# LedMatrix.net
KiCad netlist of a schematic drawn in EAGLE
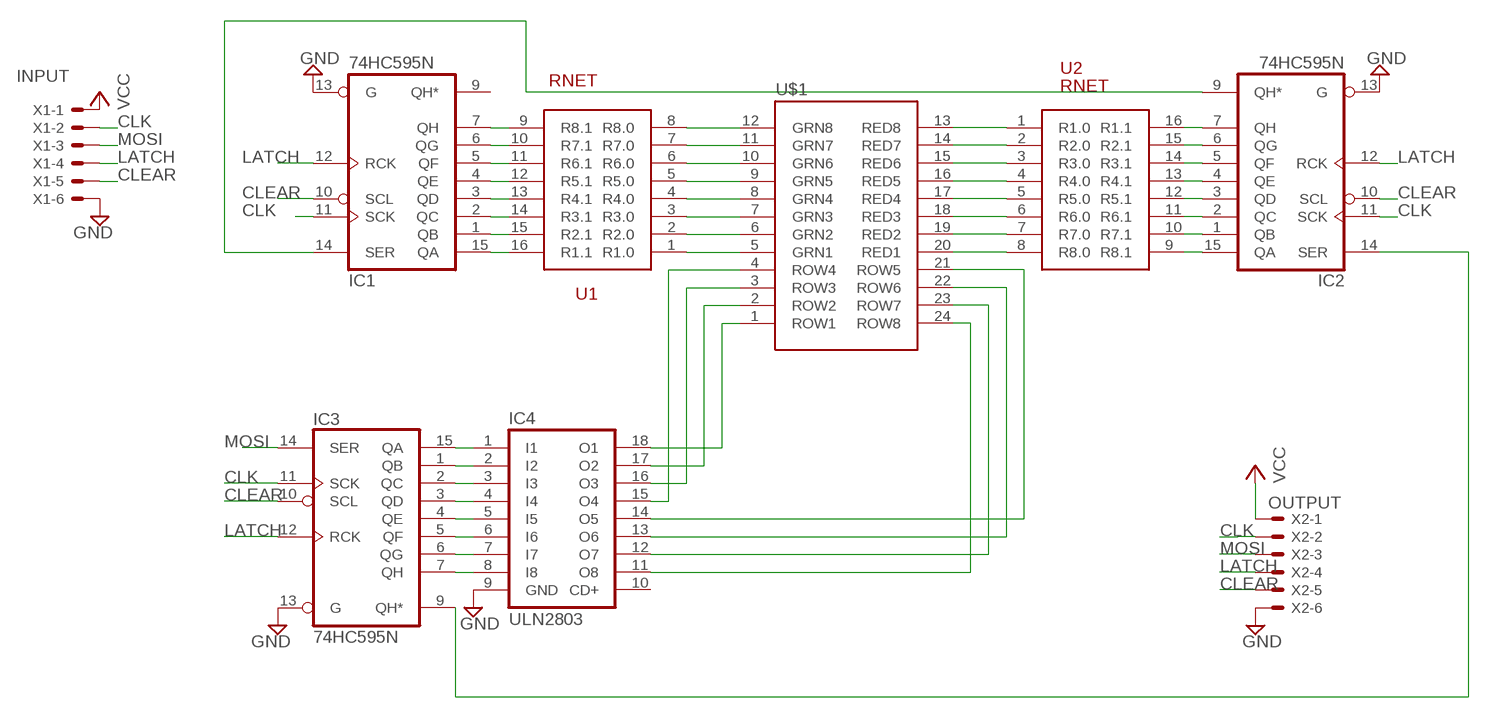
[diagram p0: schematic, sheet 1]

(export (version "E")
  (design (tool "Eeschema 10.0.6"))
  (components
    (comp (ref "IC1")
      (value "74HC595N")
      (footprint "eagle-import:DIL16")
      (libsource (lib "eagle-import") (part "74595NHC"))
    )
    (comp (ref "IC2")
      (value "74HC595N")
      (footprint "eagle-import:DIL16")
      (libsource (lib "eagle-import") (part "74595NHC"))
    )
    (comp (ref "IC3")
      (value "74HC595N")
      (footprint "eagle-import:DIL16")
      (libsource (lib "eagle-import") (part "74595NHC"))
    )
    (comp (ref "IC4")
      (value "ULN2803")
      (footprint "eagle-import:DIL18")
      (libsource (lib "eagle-import") (part "ULN2803A"))
    )
    (comp (ref "U$1")
      (value "WLG-M2088A/8EG")
      (footprint "eagle-import:WLG-M2088A_8EG")
      (libsource (lib "eagle-import") (part "WLG-M2088A/8EG"))
    )
    (comp (ref "U1")
      (value "RNET")
      (footprint "eagle-import:DIP16")
      (libsource (lib "eagle-import") (part "RESISTER-NET-R4116"))
    )
    (comp (ref "U2")
      (value "RNET")
      (footprint "eagle-import:DIP16")
      (libsource (lib "eagle-import") (part "RESISTER-NET-R4116"))
    )
    (comp (ref "X1")
      (value "INPUT")
      (footprint "eagle-import:22-23-2061")
      (libsource (lib "eagle-import") (part "22-23-2061"))
    )
    (comp (ref "X2")
      (value "OUTPUT")
      (footprint "eagle-import:22-23-2061")
      (libsource (lib "eagle-import") (part "22-23-2061"))
    )
  )
  (nets
    (net (code "1") (name "/CLEAR") (class "Default")
      (node (ref "IC1") (pin "10") (pinfunction "SCL_10") (pintype "input"))
      (node (ref "IC2") (pin "10") (pinfunction "SCL_10") (pintype "input"))
      (node (ref "IC3") (pin "10") (pinfunction "SCL_10") (pintype "input"))
      (node (ref "X1") (pin "5") (pinfunction "S_5") (pintype "passive"))
      (node (ref "X2") (pin "5") (pinfunction "S_5") (pintype "passive"))
    )
    (net (code "2") (name "/CLK") (class "Default")
      (node (ref "IC1") (pin "11") (pinfunction "SCK_11") (pintype "input"))
      (node (ref "IC2") (pin "11") (pinfunction "SCK_11") (pintype "input"))
      (node (ref "IC3") (pin "11") (pinfunction "SCK_11") (pintype "input"))
      (node (ref "X1") (pin "2") (pinfunction "S_2") (pintype "passive"))
      (node (ref "X2") (pin "2") (pinfunction "S_2") (pintype "passive"))
    )
    (net (code "3") (name "/LATCH") (class "Default")
      (node (ref "IC1") (pin "12") (pinfunction "RCK_12") (pintype "input"))
      (node (ref "IC2") (pin "12") (pinfunction "RCK_12") (pintype "input"))
      (node (ref "IC3") (pin "12") (pinfunction "RCK_12") (pintype "input"))
      (node (ref "X1") (pin "4") (pinfunction "S_4") (pintype "passive"))
      (node (ref "X2") (pin "4") (pinfunction "S_4") (pintype "passive"))
    )
    (net (code "4") (name "/MOSI") (class "Default")
      (node (ref "IC3") (pin "14") (pinfunction "SER_14") (pintype "input"))
      (node (ref "X1") (pin "3") (pinfunction "S_3") (pintype "passive"))
      (node (ref "X2") (pin "3") (pinfunction "S_3") (pintype "passive"))
    )
    (net (code "5") (name "GND") (class "Default")
      (node (ref "IC1") (pin "13") (pinfunction "G_13") (pintype "input"))
      (node (ref "IC2") (pin "13") (pinfunction "G_13") (pintype "input"))
      (node (ref "IC3") (pin "13") (pinfunction "G_13") (pintype "input"))
      (node (ref "IC4") (pin "9") (pinfunction "GND_9") (pintype "power_in"))
      (node (ref "X1") (pin "6") (pinfunction "S_6") (pintype "passive"))
      (node (ref "X2") (pin "6") (pinfunction "S_6") (pintype "passive"))
    )
    (net (code "6") (name "Net-(IC1A-QA)") (class "Default")
      (node (ref "IC1") (pin "15") (pinfunction "QA_15") (pintype "tri_state"))
      (node (ref "U1") (pin "16") (pinfunction "R1.1_16") (pintype "bidirectional"))
    )
    (net (code "7") (name "Net-(IC1A-QB)") (class "Default")
      (node (ref "IC1") (pin "1") (pinfunction "QB_1") (pintype "tri_state"))
      (node (ref "U1") (pin "15") (pinfunction "R2.1_15") (pintype "bidirectional"))
    )
    (net (code "8") (name "Net-(IC1A-QC)") (class "Default")
      (node (ref "IC1") (pin "2") (pinfunction "QC_2") (pintype "tri_state"))
      (node (ref "U1") (pin "14") (pinfunction "R3.1_14") (pintype "bidirectional"))
    )
    (net (code "9") (name "Net-(IC1A-QD)") (class "Default")
      (node (ref "IC1") (pin "3") (pinfunction "QD_3") (pintype "tri_state"))
      (node (ref "U1") (pin "13") (pinfunction "R4.1_13") (pintype "bidirectional"))
    )
    (net (code "10") (name "Net-(IC1A-QE)") (class "Default")
      (node (ref "IC1") (pin "4") (pinfunction "QE_4") (pintype "tri_state"))
      (node (ref "U1") (pin "12") (pinfunction "R5.1_12") (pintype "bidirectional"))
    )
    (net (code "11") (name "Net-(IC1A-QF)") (class "Default")
      (node (ref "IC1") (pin "5") (pinfunction "QF_5") (pintype "tri_state"))
      (node (ref "U1") (pin "11") (pinfunction "R6.1_11") (pintype "bidirectional"))
    )
    (net (code "12") (name "Net-(IC1A-QG)") (class "Default")
      (node (ref "IC1") (pin "6") (pinfunction "QG_6") (pintype "tri_state"))
      (node (ref "U1") (pin "10") (pinfunction "R7.1_10") (pintype "bidirectional"))
    )
    (net (code "13") (name "Net-(IC1A-QH)") (class "Default")
      (node (ref "IC1") (pin "7") (pinfunction "QH_7") (pintype "tri_state"))
      (node (ref "U1") (pin "9") (pinfunction "R8.1_9") (pintype "bidirectional"))
    )
    (net (code "14") (name "Net-(IC1A-SER)") (class "Default")
      (node (ref "IC1") (pin "14") (pinfunction "SER_14") (pintype "input"))
      (node (ref "IC2") (pin "9") (pinfunction "QH*_9") (pintype "tri_state"))
    )
    (net (code "15") (name "Net-(IC2A-QA)") (class "Default")
      (node (ref "IC2") (pin "15") (pinfunction "QA_15") (pintype "tri_state"))
      (node (ref "U2") (pin "9") (pinfunction "R8.1_9") (pintype "bidirectional"))
    )
    (net (code "16") (name "Net-(IC2A-QB)") (class "Default")
      (node (ref "IC2") (pin "1") (pinfunction "QB_1") (pintype "tri_state"))
      (node (ref "U2") (pin "10") (pinfunction "R7.1_10") (pintype "bidirectional"))
    )
    (net (code "17") (name "Net-(IC2A-QC)") (class "Default")
      (node (ref "IC2") (pin "2") (pinfunction "QC_2") (pintype "tri_state"))
      (node (ref "U2") (pin "11") (pinfunction "R6.1_11") (pintype "bidirectional"))
    )
    (net (code "18") (name "Net-(IC2A-QD)") (class "Default")
      (node (ref "IC2") (pin "3") (pinfunction "QD_3") (pintype "tri_state"))
      (node (ref "U2") (pin "12") (pinfunction "R5.1_12") (pintype "bidirectional"))
    )
    (net (code "19") (name "Net-(IC2A-QE)") (class "Default")
      (node (ref "IC2") (pin "4") (pinfunction "QE_4") (pintype "tri_state"))
      (node (ref "U2") (pin "13") (pinfunction "R4.1_13") (pintype "bidirectional"))
    )
    (net (code "20") (name "Net-(IC2A-QF)") (class "Default")
      (node (ref "IC2") (pin "5") (pinfunction "QF_5") (pintype "tri_state"))
      (node (ref "U2") (pin "14") (pinfunction "R3.1_14") (pintype "bidirectional"))
    )
    (net (code "21") (name "Net-(IC2A-QG)") (class "Default")
      (node (ref "IC2") (pin "6") (pinfunction "QG_6") (pintype "tri_state"))
      (node (ref "U2") (pin "15") (pinfunction "R2.1_15") (pintype "bidirectional"))
    )
    (net (code "22") (name "Net-(IC2A-QH)") (class "Default")
      (node (ref "IC2") (pin "7") (pinfunction "QH_7") (pintype "tri_state"))
      (node (ref "U2") (pin "16") (pinfunction "R1.1_16") (pintype "bidirectional"))
    )
    (net (code "23") (name "Net-(IC2A-SER)") (class "Default")
      (node (ref "IC2") (pin "14") (pinfunction "SER_14") (pintype "input"))
      (node (ref "IC3") (pin "9") (pinfunction "QH*_9") (pintype "tri_state"))
    )
    (net (code "24") (name "Net-(IC3A-QA)") (class "Default")
      (node (ref "IC3") (pin "15") (pinfunction "QA_15") (pintype "tri_state"))
      (node (ref "IC4") (pin "1") (pinfunction "I1_1") (pintype "input"))
    )
    (net (code "25") (name "Net-(IC3A-QB)") (class "Default")
      (node (ref "IC3") (pin "1") (pinfunction "QB_1") (pintype "tri_state"))
      (node (ref "IC4") (pin "2") (pinfunction "I2_2") (pintype "input"))
    )
    (net (code "26") (name "Net-(IC3A-QC)") (class "Default")
      (node (ref "IC3") (pin "2") (pinfunction "QC_2") (pintype "tri_state"))
      (node (ref "IC4") (pin "3") (pinfunction "I3_3") (pintype "input"))
    )
    (net (code "27") (name "Net-(IC3A-QD)") (class "Default")
      (node (ref "IC3") (pin "3") (pinfunction "QD_3") (pintype "tri_state"))
      (node (ref "IC4") (pin "4") (pinfunction "I4_4") (pintype "input"))
    )
    (net (code "28") (name "Net-(IC3A-QE)") (class "Default")
      (node (ref "IC3") (pin "4") (pinfunction "QE_4") (pintype "tri_state"))
      (node (ref "IC4") (pin "5") (pinfunction "I5_5") (pintype "input"))
    )
    (net (code "29") (name "Net-(IC3A-QF)") (class "Default")
      (node (ref "IC3") (pin "5") (pinfunction "QF_5") (pintype "tri_state"))
      (node (ref "IC4") (pin "6") (pinfunction "I6_6") (pintype "input"))
    )
    (net (code "30") (name "Net-(IC3A-QG)") (class "Default")
      (node (ref "IC3") (pin "6") (pinfunction "QG_6") (pintype "tri_state"))
      (node (ref "IC4") (pin "7") (pinfunction "I7_7") (pintype "input"))
    )
    (net (code "31") (name "Net-(IC3A-QH)") (class "Default")
      (node (ref "IC3") (pin "7") (pinfunction "QH_7") (pintype "tri_state"))
      (node (ref "IC4") (pin "8") (pinfunction "I8_8") (pintype "input"))
    )
    (net (code "32") (name "Net-(IC4-O1)") (class "Default")
      (node (ref "IC4") (pin "18") (pinfunction "O1_18") (pintype "open_collector"))
      (node (ref "U$1") (pin "1") (pinfunction "ROW1_1") (pintype "bidirectional"))
    )
    (net (code "33") (name "Net-(IC4-O2)") (class "Default")
      (node (ref "IC4") (pin "17") (pinfunction "O2_17") (pintype "open_collector"))
      (node (ref "U$1") (pin "2") (pinfunction "ROW2_2") (pintype "bidirectional"))
    )
    (net (code "34") (name "Net-(IC4-O3)") (class "Default")
      (node (ref "IC4") (pin "16") (pinfunction "O3_16") (pintype "open_collector"))
      (node (ref "U$1") (pin "3") (pinfunction "ROW3_3") (pintype "bidirectional"))
    )
    (net (code "35") (name "Net-(IC4-O4)") (class "Default")
      (node (ref "IC4") (pin "15") (pinfunction "O4_15") (pintype "open_collector"))
      (node (ref "U$1") (pin "4") (pinfunction "ROW4_4") (pintype "bidirectional"))
    )
    (net (code "36") (name "Net-(IC4-O5)") (class "Default")
      (node (ref "IC4") (pin "14") (pinfunction "O5_14") (pintype "open_collector"))
      (node (ref "U$1") (pin "21") (pinfunction "ROW5_21") (pintype "bidirectional"))
    )
    (net (code "37") (name "Net-(IC4-O6)") (class "Default")
      (node (ref "IC4") (pin "13") (pinfunction "O6_13") (pintype "open_collector"))
      (node (ref "U$1") (pin "22") (pinfunction "ROW6_22") (pintype "bidirectional"))
    )
    (net (code "38") (name "Net-(IC4-O7)") (class "Default")
      (node (ref "IC4") (pin "12") (pinfunction "O7_12") (pintype "open_collector"))
      (node (ref "U$1") (pin "23") (pinfunction "ROW7_23") (pintype "bidirectional"))
    )
    (net (code "39") (name "Net-(IC4-O8)") (class "Default")
      (node (ref "IC4") (pin "11") (pinfunction "O8_11") (pintype "open_collector"))
      (node (ref "U$1") (pin "24") (pinfunction "ROW8_24") (pintype "bidirectional"))
    )
    (net (code "40") (name "Net-(U$1-GRN1)") (class "Default")
      (node (ref "U$1") (pin "5") (pinfunction "GRN1_5") (pintype "bidirectional"))
      (node (ref "U1") (pin "1") (pinfunction "R1.0_1") (pintype "bidirectional"))
    )
    (net (code "41") (name "Net-(U$1-GRN2)") (class "Default")
      (node (ref "U$1") (pin "6") (pinfunction "GRN2_6") (pintype "bidirectional"))
      (node (ref "U1") (pin "2") (pinfunction "R2.0_2") (pintype "bidirectional"))
    )
    (net (code "42") (name "Net-(U$1-GRN3)") (class "Default")
      (node (ref "U$1") (pin "7") (pinfunction "GRN3_7") (pintype "bidirectional"))
      (node (ref "U1") (pin "3") (pinfunction "R3.0_3") (pintype "bidirectional"))
    )
    (net (code "43") (name "Net-(U$1-GRN4)") (class "Default")
      (node (ref "U$1") (pin "8") (pinfunction "GRN4_8") (pintype "bidirectional"))
      (node (ref "U1") (pin "4") (pinfunction "R4.0_4") (pintype "bidirectional"))
    )
    (net (code "44") (name "Net-(U$1-GRN5)") (class "Default")
      (node (ref "U$1") (pin "9") (pinfunction "GRN5_9") (pintype "bidirectional"))
      (node (ref "U1") (pin "5") (pinfunction "R5.0_5") (pintype "bidirectional"))
    )
    (net (code "45") (name "Net-(U$1-GRN6)") (class "Default")
      (node (ref "U$1") (pin "10") (pinfunction "GRN6_10") (pintype "bidirectional"))
      (node (ref "U1") (pin "6") (pinfunction "R6.0_6") (pintype "bidirectional"))
    )
    (net (code "46") (name "Net-(U$1-GRN7)") (class "Default")
      (node (ref "U$1") (pin "11") (pinfunction "GRN7_11") (pintype "bidirectional"))
      (node (ref "U1") (pin "7") (pinfunction "R7.0_7") (pintype "bidirectional"))
    )
    (net (code "47") (name "Net-(U$1-GRN8)") (class "Default")
      (node (ref "U$1") (pin "12") (pinfunction "GRN8_12") (pintype "bidirectional"))
      (node (ref "U1") (pin "8") (pinfunction "R8.0_8") (pintype "bidirectional"))
    )
    (net (code "48") (name "Net-(U$1-RED1)") (class "Default")
      (node (ref "U$1") (pin "20") (pinfunction "RED1_20") (pintype "bidirectional"))
      (node (ref "U2") (pin "8") (pinfunction "R8.0_8") (pintype "bidirectional"))
    )
    (net (code "49") (name "Net-(U$1-RED2)") (class "Default")
      (node (ref "U$1") (pin "19") (pinfunction "RED2_19") (pintype "bidirectional"))
      (node (ref "U2") (pin "7") (pinfunction "R7.0_7") (pintype "bidirectional"))
    )
    (net (code "50") (name "Net-(U$1-RED3)") (class "Default")
      (node (ref "U$1") (pin "18") (pinfunction "RED3_18") (pintype "bidirectional"))
      (node (ref "U2") (pin "6") (pinfunction "R6.0_6") (pintype "bidirectional"))
    )
    (net (code "51") (name "Net-(U$1-RED4)") (class "Default")
      (node (ref "U$1") (pin "17") (pinfunction "RED4_17") (pintype "bidirectional"))
      (node (ref "U2") (pin "5") (pinfunction "R5.0_5") (pintype "bidirectional"))
    )
    (net (code "52") (name "Net-(U$1-RED5)") (class "Default")
      (node (ref "U$1") (pin "16") (pinfunction "RED5_16") (pintype "bidirectional"))
      (node (ref "U2") (pin "4") (pinfunction "R4.0_4") (pintype "bidirectional"))
    )
    (net (code "53") (name "Net-(U$1-RED6)") (class "Default")
      (node (ref "U$1") (pin "15") (pinfunction "RED6_15") (pintype "bidirectional"))
      (node (ref "U2") (pin "3") (pinfunction "R3.0_3") (pintype "bidirectional"))
    )
    (net (code "54") (name "Net-(U$1-RED7)") (class "Default")
      (node (ref "U$1") (pin "14") (pinfunction "RED7_14") (pintype "bidirectional"))
      (node (ref "U2") (pin "2") (pinfunction "R2.0_2") (pintype "bidirectional"))
    )
    (net (code "55") (name "Net-(U$1-RED8)") (class "Default")
      (node (ref "U$1") (pin "13") (pinfunction "RED8_13") (pintype "bidirectional"))
      (node (ref "U2") (pin "1") (pinfunction "R1.0_1") (pintype "bidirectional"))
    )
    (net (code "56") (name "VCC") (class "Default")
      (node (ref "X1") (pin "1") (pinfunction "S_1") (pintype "passive"))
      (node (ref "X2") (pin "1") (pinfunction "S_1") (pintype "passive"))
    )
    (net (code "57") (name "unconnected-(IC1A-QH*-Pad9)") (class "Default")
      (node (ref "IC1") (pin "9") (pinfunction "QH*_9") (pintype "tri_state"))
    )
    (net (code "58") (name "unconnected-(IC4-CD+-Pad10)") (class "Default")
      (node (ref "IC4") (pin "10") (pinfunction "CD+_10") (pintype "passive"))
    )
  )
)
